# proto3.net
KiCad netlist of a schematic drawn in EAGLE
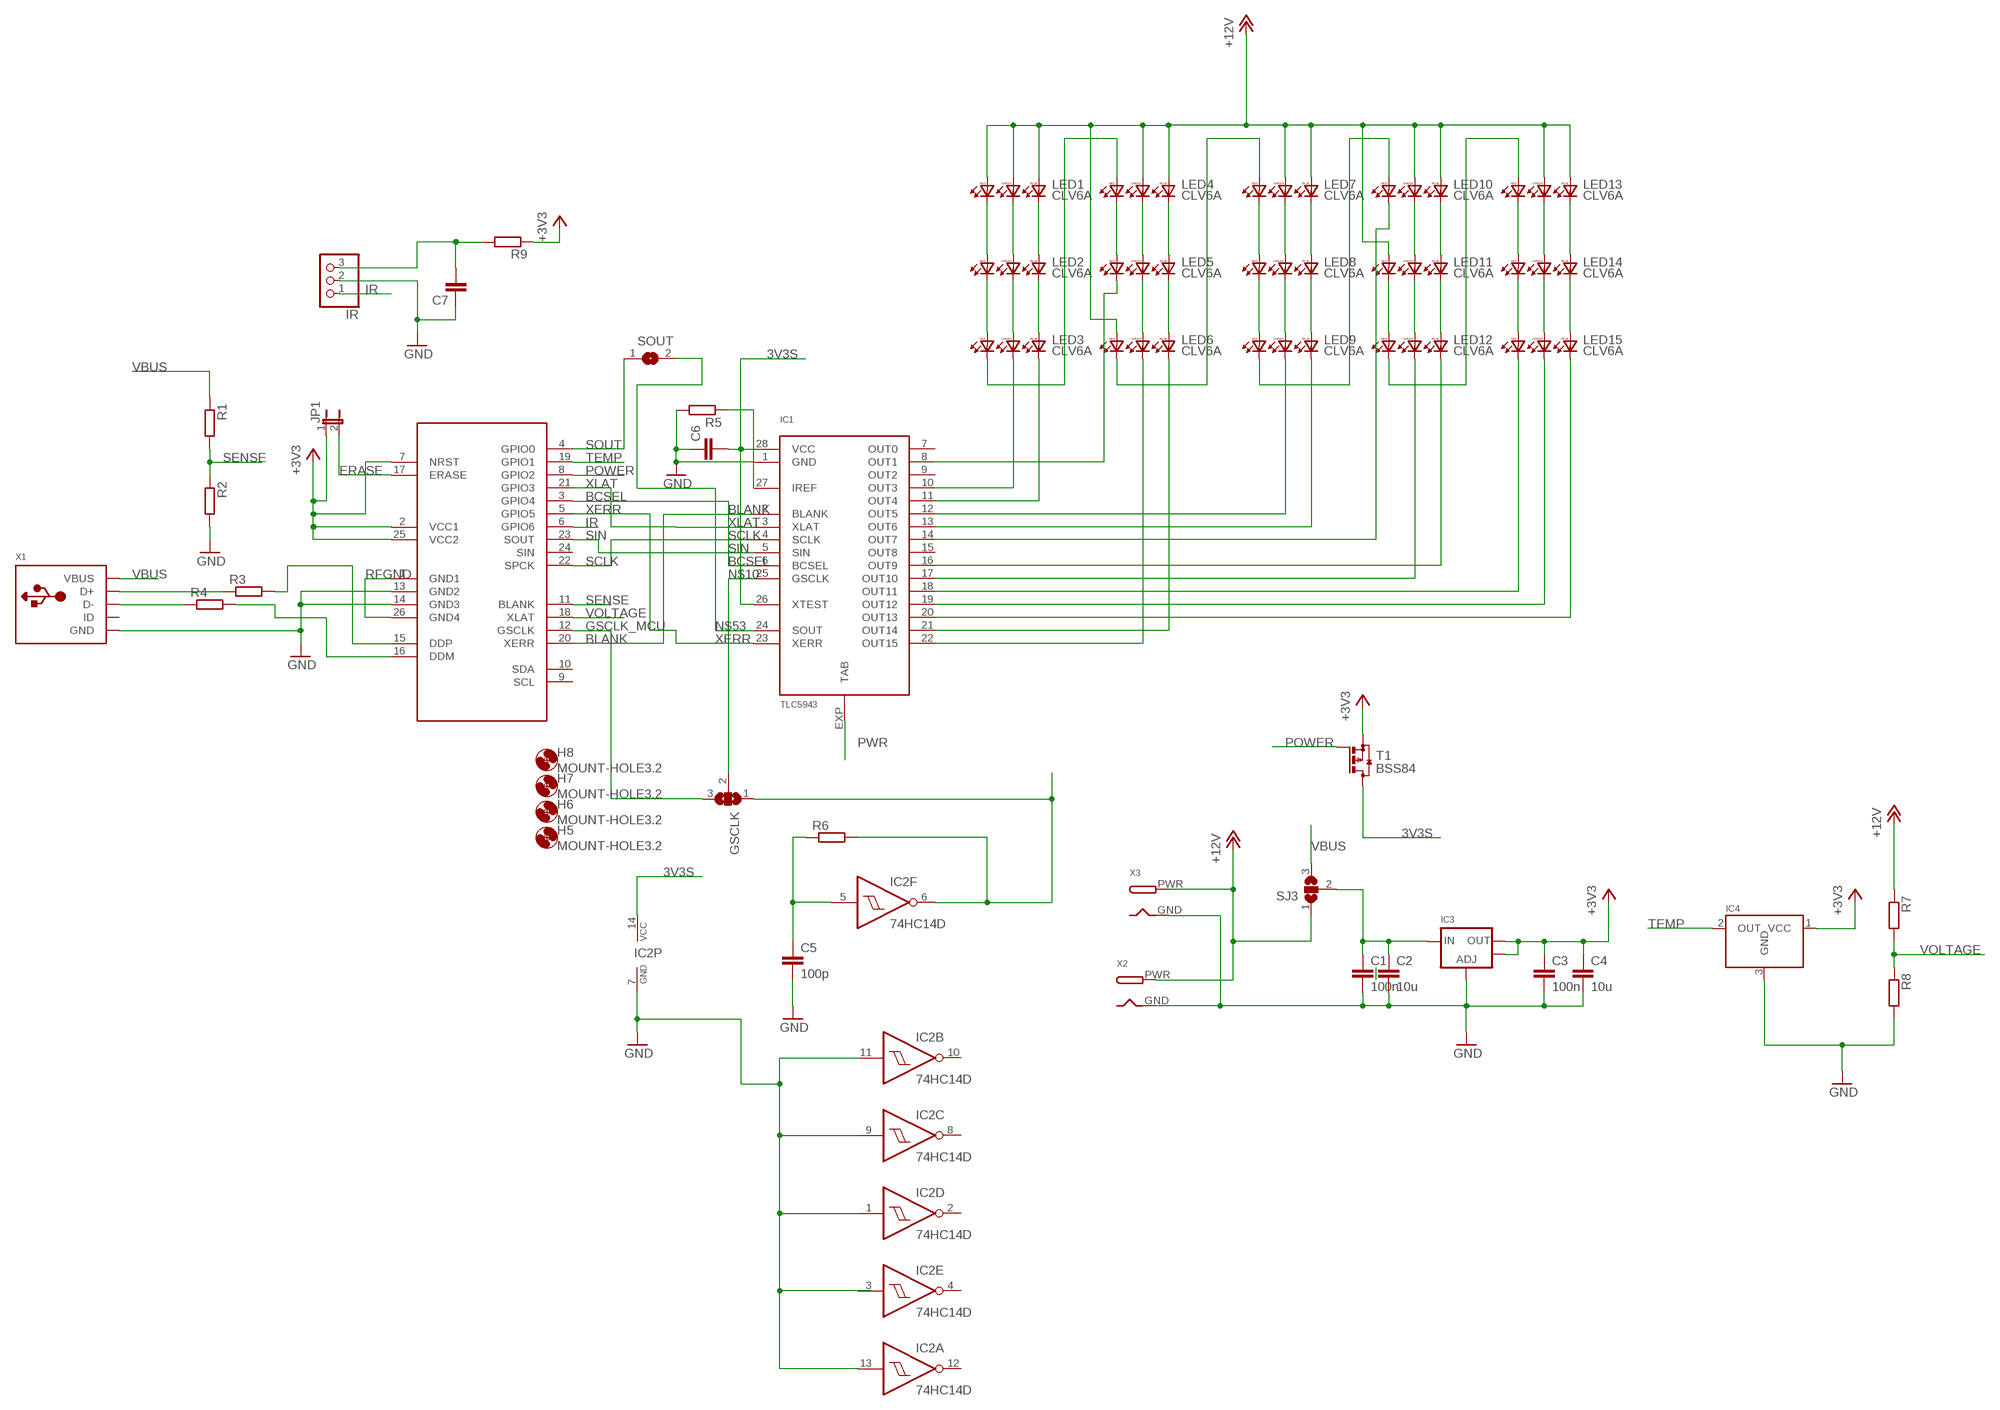
[diagram p0: schematic, sheet 1]

(export (version "E")
  (design (tool "Eeschema 10.0.6"))
  (components
    (comp (ref "C1")
      (value "100n")
      (footprint "eagle-import:C0805")
      (libsource (lib "eagle-import") (part "C-EUC0805"))
    )
    (comp (ref "C2")
      (value "10u")
      (footprint "eagle-import:C0805")
      (libsource (lib "eagle-import") (part "C-EUC0805"))
    )
    (comp (ref "C3")
      (value "100n")
      (footprint "eagle-import:C0805")
      (libsource (lib "eagle-import") (part "C-EUC0805"))
    )
    (comp (ref "C4")
      (value "10u")
      (footprint "eagle-import:C0805")
      (libsource (lib "eagle-import") (part "C-EUC0805"))
    )
    (comp (ref "C5")
      (value "100p")
      (footprint "eagle-import:C0805")
      (libsource (lib "eagle-import") (part "C-EUC0805"))
    )
    (comp (ref "C6")
      (value "C-EUC0805")
      (footprint "eagle-import:C0805")
      (libsource (lib "eagle-import") (part "C-EUC0805"))
    )
    (comp (ref "C7")
      (value "C-EUC0805")
      (footprint "eagle-import:C0805")
      (libsource (lib "eagle-import") (part "C-EUC0805"))
    )
    (comp (ref "GSCLK")
      (value "SJ2W")
      (footprint "eagle-import:SJ_2")
      (libsource (lib "eagle-import") (part "SJ2W"))
    )
    (comp (ref "H5")
      (value "MOUNT-HOLE3.2")
      (footprint "eagle-import:3,2")
      (libsource (lib "eagle-import") (part "MOUNT-HOLE3.2"))
    )
    (comp (ref "H6")
      (value "MOUNT-HOLE3.2")
      (footprint "eagle-import:3,2")
      (libsource (lib "eagle-import") (part "MOUNT-HOLE3.2"))
    )
    (comp (ref "H7")
      (value "MOUNT-HOLE3.2")
      (footprint "eagle-import:3,2")
      (libsource (lib "eagle-import") (part "MOUNT-HOLE3.2"))
    )
    (comp (ref "H8")
      (value "MOUNT-HOLE3.2")
      (footprint "eagle-import:3,2")
      (libsource (lib "eagle-import") (part "MOUNT-HOLE3.2"))
    )
    (comp (ref "IC1")
      (value "TLC5943")
      (footprint "eagle-import:HTSSOP28PWP")
      (libsource (lib "eagle-import") (part "TLC5943"))
    )
    (comp (ref "IC2")
      (value "74HC14D")
      (footprint "eagle-import:SO14")
      (libsource (lib "eagle-import") (part "7414DHC"))
    )
    (comp (ref "IC3")
      (value "LM1117SOT223-REFLOW")
      (footprint "eagle-import:SOT223-R")
      (libsource (lib "eagle-import") (part "LM1117SOT223-REFLOW"))
    )
    (comp (ref "IC4")
      (value "MCP9701T-E/TTCTREFLOW")
      (footprint "eagle-import:SOT23-R")
      (libsource (lib "eagle-import") (part "MCP9701T-E/TTCTREFLOW"))
    )
    (comp (ref "IR")
      (value "PINHD-1X3")
      (footprint "eagle-import:1X03")
      (libsource (lib "eagle-import") (part "PINHD-1X3"))
    )
    (comp (ref "JP1")
      (value "JP1E")
      (footprint "eagle-import:JP1")
      (libsource (lib "eagle-import") (part "JP1E"))
    )
    (comp (ref "LED1")
      (value "CLV6A")
      (footprint "eagle-import:PLCC6")
      (libsource (lib "eagle-import") (part "CLV6A"))
    )
    (comp (ref "LED2")
      (value "CLV6A")
      (footprint "eagle-import:PLCC6")
      (libsource (lib "eagle-import") (part "CLV6A"))
    )
    (comp (ref "LED3")
      (value "CLV6A")
      (footprint "eagle-import:PLCC6")
      (libsource (lib "eagle-import") (part "CLV6A"))
    )
    (comp (ref "LED4")
      (value "CLV6A")
      (footprint "eagle-import:PLCC6")
      (libsource (lib "eagle-import") (part "CLV6A"))
    )
    (comp (ref "LED5")
      (value "CLV6A")
      (footprint "eagle-import:PLCC6")
      (libsource (lib "eagle-import") (part "CLV6A"))
    )
    (comp (ref "LED6")
      (value "CLV6A")
      (footprint "eagle-import:PLCC6")
      (libsource (lib "eagle-import") (part "CLV6A"))
    )
    (comp (ref "LED7")
      (value "CLV6A")
      (footprint "eagle-import:PLCC6")
      (libsource (lib "eagle-import") (part "CLV6A"))
    )
    (comp (ref "LED8")
      (value "CLV6A")
      (footprint "eagle-import:PLCC6")
      (libsource (lib "eagle-import") (part "CLV6A"))
    )
    (comp (ref "LED9")
      (value "CLV6A")
      (footprint "eagle-import:PLCC6")
      (libsource (lib "eagle-import") (part "CLV6A"))
    )
    (comp (ref "LED10")
      (value "CLV6A")
      (footprint "eagle-import:PLCC6")
      (libsource (lib "eagle-import") (part "CLV6A"))
    )
    (comp (ref "LED11")
      (value "CLV6A")
      (footprint "eagle-import:PLCC6")
      (libsource (lib "eagle-import") (part "CLV6A"))
    )
    (comp (ref "LED12")
      (value "CLV6A")
      (footprint "eagle-import:PLCC6")
      (libsource (lib "eagle-import") (part "CLV6A"))
    )
    (comp (ref "LED13")
      (value "CLV6A")
      (footprint "eagle-import:PLCC6")
      (libsource (lib "eagle-import") (part "CLV6A"))
    )
    (comp (ref "LED14")
      (value "CLV6A")
      (footprint "eagle-import:PLCC6")
      (libsource (lib "eagle-import") (part "CLV6A"))
    )
    (comp (ref "LED15")
      (value "CLV6A")
      (footprint "eagle-import:PLCC6")
      (libsource (lib "eagle-import") (part "CLV6A"))
    )
    (comp (ref "R1")
      (value "R-EU_R0805")
      (footprint "eagle-import:R0805")
      (libsource (lib "eagle-import") (part "R-EU_R0805"))
    )
    (comp (ref "R2")
      (value "R-EU_R0805")
      (footprint "eagle-import:R0805")
      (libsource (lib "eagle-import") (part "R-EU_R0805"))
    )
    (comp (ref "R3")
      (value "R-EU_R0805")
      (footprint "eagle-import:R0805")
      (libsource (lib "eagle-import") (part "R-EU_R0805"))
    )
    (comp (ref "R4")
      (value "R-EU_R0805")
      (footprint "eagle-import:R0805")
      (libsource (lib "eagle-import") (part "R-EU_R0805"))
    )
    (comp (ref "R5")
      (value "R-EU_R0805")
      (footprint "eagle-import:R0805")
      (libsource (lib "eagle-import") (part "R-EU_R0805"))
    )
    (comp (ref "R6")
      (value "R-EU_R0805")
      (footprint "eagle-import:R0805")
      (libsource (lib "eagle-import") (part "R-EU_R0805"))
    )
    (comp (ref "R7")
      (value "R-EU_R0805")
      (footprint "eagle-import:R0805")
      (libsource (lib "eagle-import") (part "R-EU_R0805"))
    )
    (comp (ref "R8")
      (value "R-EU_R0805")
      (footprint "eagle-import:R0805")
      (libsource (lib "eagle-import") (part "R-EU_R0805"))
    )
    (comp (ref "R9")
      (value "R-EU_R0805")
      (footprint "eagle-import:R0805")
      (libsource (lib "eagle-import") (part "R-EU_R0805"))
    )
    (comp (ref "SJ3")
      (value "SJ2W")
      (footprint "eagle-import:SJ_2")
      (libsource (lib "eagle-import") (part "SJ2W"))
    )
    (comp (ref "SOUT")
      (value "SJ")
      (footprint "eagle-import:SJ")
      (libsource (lib "eagle-import") (part "SJ"))
    )
    (comp (ref "T1")
      (value "BSS84")
      (footprint "eagle-import:SOT23")
      (libsource (lib "eagle-import") (part "BSS84"))
    )
    (comp (ref "U$1")
      (value "RFBOARD")
      (footprint "eagle-import:RFBOARD")
      (libsource (lib "eagle-import") (part "RFBOARD"))
    )
    (comp (ref "X1")
      (value "USBMINIB")
      (footprint "eagle-import:USB-MINIB")
      (libsource (lib "eagle-import") (part "USBMINIB"))
    )
    (comp (ref "X2")
      (value "DCBARRELPTH")
      (footprint "eagle-import:DCJACK_2MM_PTH")
      (libsource (lib "eagle-import") (part "DCBARRELPTH"))
    )
    (comp (ref "X3")
      (value "DCBARRELPTH")
      (footprint "eagle-import:DCJACK_2MM_PTH")
      (libsource (lib "eagle-import") (part "DCBARRELPTH"))
    )
  )
  (nets
    (net (code "1") (name "+3V3") (class "Default")
      (node (ref "C3") (pin "1") (pinfunction "1_1") (pintype "passive"))
      (node (ref "C4") (pin "1") (pinfunction "1_1") (pintype "passive"))
      (node (ref "IC3") (pin "2") (pinfunction "OUT_2") (pintype "passive"))
      (node (ref "IC3") (pin "4") (pinfunction "OUT1_4") (pintype "passive"))
      (node (ref "IC4") (pin "1") (pinfunction "VCC_1") (pintype "power_in"))
      (node (ref "JP1") (pin "1") (pinfunction "1_1") (pintype "passive"))
      (node (ref "R9") (pin "1") (pinfunction "1_1") (pintype "passive"))
      (node (ref "T1") (pin "2") (pinfunction "S_2") (pintype "passive"))
      (node (ref "U$1") (pin "2") (pinfunction "VCC1_2") (pintype "bidirectional"))
      (node (ref "U$1") (pin "25") (pinfunction "VCC2_25") (pintype "bidirectional"))
      (node (ref "U$1") (pin "7") (pinfunction "NRST_7") (pintype "bidirectional"))
    )
    (net (code "2") (name "+12V") (class "Default")
      (node (ref "LED1") (pin "4") (pinfunction "RA_4") (pintype "passive"))
      (node (ref "LED1") (pin "5") (pinfunction "GA_5") (pintype "passive"))
      (node (ref "LED1") (pin "6") (pinfunction "BA_6") (pintype "passive"))
      (node (ref "LED10") (pin "5") (pinfunction "GA_5") (pintype "passive"))
      (node (ref "LED10") (pin "6") (pinfunction "BA_6") (pintype "passive"))
      (node (ref "LED11") (pin "4") (pinfunction "RA_4") (pintype "passive"))
      (node (ref "LED13") (pin "5") (pinfunction "GA_5") (pintype "passive"))
      (node (ref "LED13") (pin "6") (pinfunction "BA_6") (pintype "passive"))
      (node (ref "LED4") (pin "5") (pinfunction "GA_5") (pintype "passive"))
      (node (ref "LED4") (pin "6") (pinfunction "BA_6") (pintype "passive"))
      (node (ref "LED6") (pin "4") (pinfunction "RA_4") (pintype "passive"))
      (node (ref "LED7") (pin "5") (pinfunction "GA_5") (pintype "passive"))
      (node (ref "LED7") (pin "6") (pinfunction "BA_6") (pintype "passive"))
      (node (ref "R7") (pin "1") (pinfunction "1_1") (pintype "passive"))
      (node (ref "SJ3") (pin "1") (pinfunction "1_1") (pintype "passive"))
      (node (ref "X2") (pin "PWR") (pinfunction "PWR_PWR") (pintype "power_in"))
      (node (ref "X3") (pin "PWR") (pinfunction "PWR_PWR") (pintype "power_in"))
    )
    (net (code "3") (name "/3V3S") (class "Default")
      (node (ref "C6") (pin "2") (pinfunction "2_2") (pintype "passive"))
      (node (ref "IC1") (pin "26") (pinfunction "XTEST_26") (pintype "bidirectional"))
      (node (ref "IC1") (pin "28") (pinfunction "VCC_28") (pintype "bidirectional"))
      (node (ref "IC2") (pin "14") (pinfunction "VCC_14") (pintype "power_in"))
      (node (ref "T1") (pin "3") (pinfunction "D_3") (pintype "passive"))
    )
    (net (code "4") (name "/BCSEL") (class "Default")
      (node (ref "IC1") (pin "6") (pinfunction "BCSEL_6") (pintype "bidirectional"))
      (node (ref "U$1") (pin "3") (pinfunction "GPIO4_3") (pintype "bidirectional"))
    )
    (net (code "5") (name "/BLANK") (class "Default")
      (node (ref "IC1") (pin "2") (pinfunction "BLANK_2") (pintype "bidirectional"))
      (node (ref "U$1") (pin "20") (pinfunction "XERR_20") (pintype "bidirectional"))
    )
    (net (code "6") (name "/ERASE") (class "Default")
      (node (ref "JP1") (pin "2") (pinfunction "2_2") (pintype "passive"))
      (node (ref "U$1") (pin "17") (pinfunction "ERASE_17") (pintype "bidirectional"))
    )
    (net (code "7") (name "/GSCLK_MCU") (class "Default")
      (node (ref "GSCLK") (pin "3") (pinfunction "3_3") (pintype "passive"))
      (node (ref "U$1") (pin "12") (pinfunction "GSCLK_12") (pintype "bidirectional"))
    )
    (net (code "8") (name "/IR") (class "Default")
      (node (ref "IR") (pin "1") (pinfunction "1_1") (pintype "passive"))
      (node (ref "U$1") (pin "6") (pinfunction "GPIO6_6") (pintype "bidirectional"))
    )
    (net (code "9") (name "/N$10") (class "Default")
      (node (ref "GSCLK") (pin "2") (pinfunction "2_2") (pintype "passive"))
      (node (ref "IC1") (pin "25") (pinfunction "GSCLK_25") (pintype "bidirectional"))
    )
    (net (code "10") (name "/N$53") (class "Default")
      (node (ref "IC1") (pin "24") (pinfunction "SOUT_24") (pintype "bidirectional"))
      (node (ref "SOUT") (pin "2") (pinfunction "2_2") (pintype "passive"))
    )
    (net (code "11") (name "/POWER") (class "Default")
      (node (ref "T1") (pin "1") (pinfunction "G_1") (pintype "passive"))
      (node (ref "U$1") (pin "8") (pinfunction "GPIO2_8") (pintype "bidirectional"))
    )
    (net (code "12") (name "/PWR") (class "Default")
      (node (ref "IC1") (pin "EXP") (pinfunction "TAB_EXP") (pintype "bidirectional"))
    )
    (net (code "13") (name "/RFGND") (class "Default")
      (node (ref "U$1") (pin "1") (pinfunction "GND1_1") (pintype "bidirectional"))
      (node (ref "U$1") (pin "26") (pinfunction "GND4_26") (pintype "bidirectional"))
    )
    (net (code "14") (name "/SCLK") (class "Default")
      (node (ref "IC1") (pin "4") (pinfunction "SCLK_4") (pintype "bidirectional"))
      (node (ref "U$1") (pin "22") (pinfunction "SPCK_22") (pintype "bidirectional"))
    )
    (net (code "15") (name "/SENSE") (class "Default")
      (node (ref "R1") (pin "2") (pinfunction "2_2") (pintype "passive"))
      (node (ref "R2") (pin "1") (pinfunction "1_1") (pintype "passive"))
      (node (ref "U$1") (pin "11") (pinfunction "BLANK_11") (pintype "bidirectional"))
    )
    (net (code "16") (name "/SIN") (class "Default")
      (node (ref "IC1") (pin "5") (pinfunction "SIN_5") (pintype "bidirectional"))
      (node (ref "U$1") (pin "23") (pinfunction "SOUT_23") (pintype "bidirectional"))
    )
    (net (code "17") (name "/SOUT") (class "Default")
      (node (ref "SOUT") (pin "1") (pinfunction "1_1") (pintype "passive"))
      (node (ref "U$1") (pin "4") (pinfunction "GPIO0_4") (pintype "bidirectional"))
    )
    (net (code "18") (name "/TEMP") (class "Default")
      (node (ref "IC4") (pin "2") (pinfunction "OUT_2") (pintype "bidirectional"))
      (node (ref "U$1") (pin "19") (pinfunction "GPIO1_19") (pintype "bidirectional"))
    )
    (net (code "19") (name "/VBUS") (class "Default")
      (node (ref "R1") (pin "1") (pinfunction "1_1") (pintype "passive"))
      (node (ref "SJ3") (pin "3") (pinfunction "3_3") (pintype "passive"))
      (node (ref "X1") (pin "VBUS") (pinfunction "VBUS_VBUS") (pintype "power_in"))
    )
    (net (code "20") (name "/VOLTAGE") (class "Default")
      (node (ref "R7") (pin "2") (pinfunction "2_2") (pintype "passive"))
      (node (ref "R8") (pin "1") (pinfunction "1_1") (pintype "passive"))
      (node (ref "U$1") (pin "18") (pinfunction "XLAT_18") (pintype "bidirectional"))
    )
    (net (code "21") (name "/XERR") (class "Default")
      (node (ref "IC1") (pin "23") (pinfunction "XERR_23") (pintype "bidirectional"))
      (node (ref "U$1") (pin "5") (pinfunction "GPIO5_5") (pintype "bidirectional"))
    )
    (net (code "22") (name "/XLAT") (class "Default")
      (node (ref "IC1") (pin "3") (pinfunction "XLAT_3") (pintype "bidirectional"))
      (node (ref "U$1") (pin "21") (pinfunction "GPIO3_21") (pintype "bidirectional"))
    )
    (net (code "23") (name "GND") (class "Default")
      (node (ref "C1") (pin "2") (pinfunction "2_2") (pintype "passive"))
      (node (ref "C2") (pin "2") (pinfunction "2_2") (pintype "passive"))
      (node (ref "C3") (pin "2") (pinfunction "2_2") (pintype "passive"))
      (node (ref "C4") (pin "2") (pinfunction "2_2") (pintype "passive"))
      (node (ref "C5") (pin "2") (pinfunction "2_2") (pintype "passive"))
      (node (ref "C6") (pin "1") (pinfunction "1_1") (pintype "passive"))
      (node (ref "C7") (pin "1") (pinfunction "1_1") (pintype "passive"))
      (node (ref "IC1") (pin "1") (pinfunction "GND_1") (pintype "bidirectional"))
      (node (ref "IC2") (pin "1") (pinfunction "I_1") (pintype "input"))
      (node (ref "IC2") (pin "11") (pinfunction "I_11") (pintype "input"))
      (node (ref "IC2") (pin "13") (pinfunction "I_13") (pintype "input"))
      (node (ref "IC2") (pin "7") (pinfunction "GND_7") (pintype "power_in"))
      (node (ref "IC2") (pin "9") (pinfunction "I_9") (pintype "input"))
      (node (ref "IC3") (pin "1") (pinfunction "ADJ_1") (pintype "input"))
      (node (ref "IC4") (pin "3") (pinfunction "GND_3") (pintype "power_in"))
      (node (ref "IR") (pin "2") (pinfunction "2_2") (pintype "passive"))
      (node (ref "R2") (pin "2") (pinfunction "2_2") (pintype "passive"))
      (node (ref "R5") (pin "2") (pinfunction "2_2") (pintype "passive"))
      (node (ref "R8") (pin "2") (pinfunction "2_2") (pintype "passive"))
      (node (ref "U$1") (pin "13") (pinfunction "GND2_13") (pintype "bidirectional"))
      (node (ref "U$1") (pin "14") (pinfunction "GND3_14") (pintype "bidirectional"))
      (node (ref "X1") (pin "GND") (pinfunction "GND_GND") (pintype "power_in"))
      (node (ref "X2") (pin "GND") (pinfunction "GND_GND") (pintype "power_in"))
      (node (ref "X3") (pin "GND") (pinfunction "GND_GND") (pintype "power_in"))
    )
    (net (code "24") (name "Net-(C7-Pad2)") (class "Default")
      (node (ref "C7") (pin "2") (pinfunction "2_2") (pintype "passive"))
      (node (ref "IR") (pin "3") (pinfunction "3_3") (pintype "passive"))
      (node (ref "R9") (pin "2") (pinfunction "2_2") (pintype "passive"))
    )
    (net (code "25") (name "Net-(IC1-IREF)") (class "Default")
      (node (ref "IC1") (pin "27") (pinfunction "IREF_27") (pintype "bidirectional"))
      (node (ref "R5") (pin "1") (pinfunction "1_1") (pintype "passive"))
    )
    (net (code "26") (name "Net-(IC1-OUT1)") (class "Default")
      (node (ref "IC1") (pin "8") (pinfunction "OUT1_8") (pintype "bidirectional"))
      (node (ref "LED5") (pin "3") (pinfunction "RC_3") (pintype "passive"))
    )
    (net (code "27") (name "Net-(IC1-OUT3)") (class "Default")
      (node (ref "IC1") (pin "10") (pinfunction "OUT3_10") (pintype "bidirectional"))
      (node (ref "LED3") (pin "2") (pinfunction "GC_2") (pintype "passive"))
    )
    (net (code "28") (name "Net-(IC1-OUT4)") (class "Default")
      (node (ref "IC1") (pin "11") (pinfunction "OUT4_11") (pintype "bidirectional"))
      (node (ref "LED3") (pin "1") (pinfunction "BC_1") (pintype "passive"))
    )
    (net (code "29") (name "Net-(IC1-OUT5)") (class "Default")
      (node (ref "IC1") (pin "12") (pinfunction "OUT5_12") (pintype "bidirectional"))
      (node (ref "LED9") (pin "2") (pinfunction "GC_2") (pintype "passive"))
    )
    (net (code "30") (name "Net-(IC1-OUT6)") (class "Default")
      (node (ref "IC1") (pin "13") (pinfunction "OUT6_13") (pintype "bidirectional"))
      (node (ref "LED9") (pin "1") (pinfunction "BC_1") (pintype "passive"))
    )
    (net (code "31") (name "Net-(IC1-OUT7)") (class "Default")
      (node (ref "IC1") (pin "14") (pinfunction "OUT7_14") (pintype "bidirectional"))
      (node (ref "LED10") (pin "3") (pinfunction "RC_3") (pintype "passive"))
    )
    (net (code "32") (name "Net-(IC1-OUT9)") (class "Default")
      (node (ref "IC1") (pin "16") (pinfunction "OUT9_16") (pintype "bidirectional"))
      (node (ref "LED12") (pin "1") (pinfunction "BC_1") (pintype "passive"))
    )
    (net (code "33") (name "Net-(IC1-OUT10)") (class "Default")
      (node (ref "IC1") (pin "17") (pinfunction "OUT10_17") (pintype "bidirectional"))
      (node (ref "LED12") (pin "2") (pinfunction "GC_2") (pintype "passive"))
    )
    (net (code "34") (name "Net-(IC1-OUT11)") (class "Default")
      (node (ref "IC1") (pin "18") (pinfunction "OUT11_18") (pintype "bidirectional"))
      (node (ref "LED15") (pin "3") (pinfunction "RC_3") (pintype "passive"))
    )
    (net (code "35") (name "Net-(IC1-OUT12)") (class "Default")
      (node (ref "IC1") (pin "19") (pinfunction "OUT12_19") (pintype "bidirectional"))
      (node (ref "LED15") (pin "2") (pinfunction "GC_2") (pintype "passive"))
    )
    (net (code "36") (name "Net-(IC1-OUT13)") (class "Default")
      (node (ref "IC1") (pin "20") (pinfunction "OUT13_20") (pintype "bidirectional"))
      (node (ref "LED15") (pin "1") (pinfunction "BC_1") (pintype "passive"))
    )
    (net (code "37") (name "Net-(IC1-OUT14)") (class "Default")
      (node (ref "IC1") (pin "21") (pinfunction "OUT14_21") (pintype "bidirectional"))
      (node (ref "LED6") (pin "1") (pinfunction "BC_1") (pintype "passive"))
    )
    (net (code "38") (name "Net-(IC1-OUT15)") (class "Default")
      (node (ref "IC1") (pin "22") (pinfunction "OUT15_22") (pintype "bidirectional"))
      (node (ref "LED6") (pin "2") (pinfunction "GC_2") (pintype "passive"))
    )
    (net (code "39") (name "Net-(IC2F-I)") (class "Default")
      (node (ref "C5") (pin "1") (pinfunction "1_1") (pintype "passive"))
      (node (ref "IC2") (pin "5") (pinfunction "I_5") (pintype "input"))
      (node (ref "R6") (pin "1") (pinfunction "1_1") (pintype "passive"))
    )
    (net (code "40") (name "Net-(IC2F-O)") (class "Default")
      (node (ref "GSCLK") (pin "1") (pinfunction "1_1") (pintype "passive"))
      (node (ref "IC2") (pin "6") (pinfunction "O_6") (pintype "output"))
      (node (ref "R6") (pin "2") (pinfunction "2_2") (pintype "passive"))
    )
    (net (code "41") (name "Net-(IC3-IN)") (class "Default")
      (node (ref "C1") (pin "1") (pinfunction "1_1") (pintype "passive"))
      (node (ref "C2") (pin "1") (pinfunction "1_1") (pintype "passive"))
      (node (ref "IC3") (pin "3") (pinfunction "IN_3") (pintype "input"))
      (node (ref "SJ3") (pin "2") (pinfunction "2_2") (pintype "passive"))
    )
    (net (code "42") (name "Net-(LED1-BC)") (class "Default")
      (node (ref "LED1") (pin "1") (pinfunction "BC_1") (pintype "passive"))
      (node (ref "LED2") (pin "6") (pinfunction "BA_6") (pintype "passive"))
    )
    (net (code "43") (name "Net-(LED1-GC)") (class "Default")
      (node (ref "LED1") (pin "2") (pinfunction "GC_2") (pintype "passive"))
      (node (ref "LED2") (pin "5") (pinfunction "GA_5") (pintype "passive"))
    )
    (net (code "44") (name "Net-(LED1-RC)") (class "Default")
      (node (ref "LED1") (pin "3") (pinfunction "RC_3") (pintype "passive"))
      (node (ref "LED2") (pin "4") (pinfunction "RA_4") (pintype "passive"))
    )
    (net (code "45") (name "Net-(LED2-BC)") (class "Default")
      (node (ref "LED2") (pin "1") (pinfunction "BC_1") (pintype "passive"))
      (node (ref "LED3") (pin "6") (pinfunction "BA_6") (pintype "passive"))
    )
    (net (code "46") (name "Net-(LED2-GC)") (class "Default")
      (node (ref "LED2") (pin "2") (pinfunction "GC_2") (pintype "passive"))
      (node (ref "LED3") (pin "5") (pinfunction "GA_5") (pintype "passive"))
    )
    (net (code "47") (name "Net-(LED2-RC)") (class "Default")
      (node (ref "LED2") (pin "3") (pinfunction "RC_3") (pintype "passive"))
      (node (ref "LED3") (pin "4") (pinfunction "RA_4") (pintype "passive"))
    )
    (net (code "48") (name "Net-(LED3-RC)") (class "Default")
      (node (ref "LED3") (pin "3") (pinfunction "RC_3") (pintype "passive"))
      (node (ref "LED4") (pin "4") (pinfunction "RA_4") (pintype "passive"))
    )
    (net (code "49") (name "Net-(LED4-BC)") (class "Default")
      (node (ref "LED4") (pin "1") (pinfunction "BC_1") (pintype "passive"))
      (node (ref "LED5") (pin "6") (pinfunction "BA_6") (pintype "passive"))
    )
    (net (code "50") (name "Net-(LED4-GC)") (class "Default")
      (node (ref "LED4") (pin "2") (pinfunction "GC_2") (pintype "passive"))
      (node (ref "LED5") (pin "5") (pinfunction "GA_5") (pintype "passive"))
    )
    (net (code "51") (name "Net-(LED4-RC)") (class "Default")
      (node (ref "LED4") (pin "3") (pinfunction "RC_3") (pintype "passive"))
      (node (ref "LED5") (pin "4") (pinfunction "RA_4") (pintype "passive"))
    )
    (net (code "52") (name "Net-(LED5-BC)") (class "Default")
      (node (ref "LED5") (pin "1") (pinfunction "BC_1") (pintype "passive"))
      (node (ref "LED6") (pin "6") (pinfunction "BA_6") (pintype "passive"))
    )
    (net (code "53") (name "Net-(LED5-GC)") (class "Default")
      (node (ref "LED5") (pin "2") (pinfunction "GC_2") (pintype "passive"))
      (node (ref "LED6") (pin "5") (pinfunction "GA_5") (pintype "passive"))
    )
    (net (code "54") (name "Net-(LED6-RC)") (class "Default")
      (node (ref "LED6") (pin "3") (pinfunction "RC_3") (pintype "passive"))
      (node (ref "LED7") (pin "4") (pinfunction "RA_4") (pintype "passive"))
    )
    (net (code "55") (name "Net-(LED7-BC)") (class "Default")
      (node (ref "LED7") (pin "1") (pinfunction "BC_1") (pintype "passive"))
      (node (ref "LED8") (pin "6") (pinfunction "BA_6") (pintype "passive"))
    )
    (net (code "56") (name "Net-(LED7-GC)") (class "Default")
      (node (ref "LED7") (pin "2") (pinfunction "GC_2") (pintype "passive"))
      (node (ref "LED8") (pin "5") (pinfunction "GA_5") (pintype "passive"))
    )
    (net (code "57") (name "Net-(LED7-RC)") (class "Default")
      (node (ref "LED7") (pin "3") (pinfunction "RC_3") (pintype "passive"))
      (node (ref "LED8") (pin "4") (pinfunction "RA_4") (pintype "passive"))
    )
    (net (code "58") (name "Net-(LED8-BC)") (class "Default")
      (node (ref "LED8") (pin "1") (pinfunction "BC_1") (pintype "passive"))
      (node (ref "LED9") (pin "6") (pinfunction "BA_6") (pintype "passive"))
    )
    (net (code "59") (name "Net-(LED8-GC)") (class "Default")
      (node (ref "LED8") (pin "2") (pinfunction "GC_2") (pintype "passive"))
      (node (ref "LED9") (pin "5") (pinfunction "GA_5") (pintype "passive"))
    )
    (net (code "60") (name "Net-(LED8-RC)") (class "Default")
      (node (ref "LED8") (pin "3") (pinfunction "RC_3") (pintype "passive"))
      (node (ref "LED9") (pin "4") (pinfunction "RA_4") (pintype "passive"))
    )
    (net (code "61") (name "Net-(LED10-BC)") (class "Default")
      (node (ref "LED10") (pin "1") (pinfunction "BC_1") (pintype "passive"))
      (node (ref "LED11") (pin "6") (pinfunction "BA_6") (pintype "passive"))
    )
    (net (code "62") (name "Net-(LED10-GC)") (class "Default")
      (node (ref "LED10") (pin "2") (pinfunction "GC_2") (pintype "passive"))
      (node (ref "LED11") (pin "5") (pinfunction "GA_5") (pintype "passive"))
    )
    (net (code "63") (name "Net-(LED10-RA)") (class "Default")
      (node (ref "LED10") (pin "4") (pinfunction "RA_4") (pintype "passive"))
      (node (ref "LED9") (pin "3") (pinfunction "RC_3") (pintype "passive"))
    )
    (net (code "64") (name "Net-(LED11-BC)") (class "Default")
      (node (ref "LED11") (pin "1") (pinfunction "BC_1") (pintype "passive"))
      (node (ref "LED12") (pin "6") (pinfunction "BA_6") (pintype "passive"))
    )
    (net (code "65") (name "Net-(LED11-GC)") (class "Default")
      (node (ref "LED11") (pin "2") (pinfunction "GC_2") (pintype "passive"))
      (node (ref "LED12") (pin "5") (pinfunction "GA_5") (pintype "passive"))
    )
    (net (code "66") (name "Net-(LED11-RC)") (class "Default")
      (node (ref "LED11") (pin "3") (pinfunction "RC_3") (pintype "passive"))
      (node (ref "LED12") (pin "4") (pinfunction "RA_4") (pintype "passive"))
    )
    (net (code "67") (name "Net-(LED12-RC)") (class "Default")
      (node (ref "LED12") (pin "3") (pinfunction "RC_3") (pintype "passive"))
      (node (ref "LED13") (pin "4") (pinfunction "RA_4") (pintype "passive"))
    )
    (net (code "68") (name "Net-(LED13-BC)") (class "Default")
      (node (ref "LED13") (pin "1") (pinfunction "BC_1") (pintype "passive"))
      (node (ref "LED14") (pin "6") (pinfunction "BA_6") (pintype "passive"))
    )
    (net (code "69") (name "Net-(LED13-GC)") (class "Default")
      (node (ref "LED13") (pin "2") (pinfunction "GC_2") (pintype "passive"))
      (node (ref "LED14") (pin "5") (pinfunction "GA_5") (pintype "passive"))
    )
    (net (code "70") (name "Net-(LED13-RC)") (class "Default")
      (node (ref "LED13") (pin "3") (pinfunction "RC_3") (pintype "passive"))
      (node (ref "LED14") (pin "4") (pinfunction "RA_4") (pintype "passive"))
    )
    (net (code "71") (name "Net-(LED14-BC)") (class "Default")
      (node (ref "LED14") (pin "1") (pinfunction "BC_1") (pintype "passive"))
      (node (ref "LED15") (pin "6") (pinfunction "BA_6") (pintype "passive"))
    )
    (net (code "72") (name "Net-(LED14-GC)") (class "Default")
      (node (ref "LED14") (pin "2") (pinfunction "GC_2") (pintype "passive"))
      (node (ref "LED15") (pin "5") (pinfunction "GA_5") (pintype "passive"))
    )
    (net (code "73") (name "Net-(LED14-RC)") (class "Default")
      (node (ref "LED14") (pin "3") (pinfunction "RC_3") (pintype "passive"))
      (node (ref "LED15") (pin "4") (pinfunction "RA_4") (pintype "passive"))
    )
    (net (code "74") (name "Net-(R3-Pad1)") (class "Default")
      (node (ref "R3") (pin "1") (pinfunction "1_1") (pintype "passive"))
      (node (ref "X1") (pin "D+") (pinfunction "D+_D+") (pintype "bidirectional"))
    )
    (net (code "75") (name "Net-(R4-Pad1)") (class "Default")
      (node (ref "R4") (pin "1") (pinfunction "1_1") (pintype "passive"))
      (node (ref "X1") (pin "D-") (pinfunction "D-_D-") (pintype "bidirectional"))
    )
    (net (code "76") (name "Net-(U$1-DDM)") (class "Default")
      (node (ref "R4") (pin "2") (pinfunction "2_2") (pintype "passive"))
      (node (ref "U$1") (pin "16") (pinfunction "DDM_16") (pintype "bidirectional"))
    )
    (net (code "77") (name "Net-(U$1-DDP)") (class "Default")
      (node (ref "R3") (pin "2") (pinfunction "2_2") (pintype "passive"))
      (node (ref "U$1") (pin "15") (pinfunction "DDP_15") (pintype "bidirectional"))
    )
    (net (code "78") (name "unconnected-(IC1-OUT0-Pad7)") (class "Default")
      (node (ref "IC1") (pin "7") (pinfunction "OUT0_7") (pintype "bidirectional"))
    )
    (net (code "79") (name "unconnected-(IC1-OUT2-Pad9)") (class "Default")
      (node (ref "IC1") (pin "9") (pinfunction "OUT2_9") (pintype "bidirectional"))
    )
    (net (code "80") (name "unconnected-(IC1-OUT8-Pad15)") (class "Default")
      (node (ref "IC1") (pin "15") (pinfunction "OUT8_15") (pintype "bidirectional"))
    )
    (net (code "81") (name "unconnected-(IC2A-O-Pad12)") (class "Default")
      (node (ref "IC2") (pin "12") (pinfunction "O_12") (pintype "output"))
    )
    (net (code "82") (name "unconnected-(IC2B-O-Pad10)") (class "Default")
      (node (ref "IC2") (pin "10") (pinfunction "O_10") (pintype "output"))
    )
    (net (code "83") (name "unconnected-(IC2C-O-Pad8)") (class "Default")
      (node (ref "IC2") (pin "8") (pinfunction "O_8") (pintype "output"))
    )
    (net (code "84") (name "unconnected-(IC2D-O-Pad2)") (class "Default")
      (node (ref "IC2") (pin "2") (pinfunction "O_2") (pintype "output"))
    )
    (net (code "85") (name "unconnected-(IC2E-I-Pad3)") (class "Default")
      (node (ref "IC2") (pin "3") (pinfunction "I_3") (pintype "input"))
    )
    (net (code "86") (name "unconnected-(IC2E-O-Pad4)") (class "Default")
      (node (ref "IC2") (pin "4") (pinfunction "O_4") (pintype "output"))
    )
    (net (code "87") (name "unconnected-(U$1-SCL-Pad9)") (class "Default")
      (node (ref "U$1") (pin "9") (pinfunction "SCL_9") (pintype "bidirectional"))
    )
    (net (code "88") (name "unconnected-(U$1-SDA-Pad10)") (class "Default")
      (node (ref "U$1") (pin "10") (pinfunction "SDA_10") (pintype "bidirectional"))
    )
    (net (code "89") (name "unconnected-(U$1-SIN-Pad24)") (class "Default")
      (node (ref "U$1") (pin "24") (pinfunction "SIN_24") (pintype "bidirectional"))
    )
    (net (code "90") (name "unconnected-(X1-PadID)") (class "Default")
      (node (ref "X1") (pin "ID") (pinfunction "ID_ID") (pintype "bidirectional"))
    )
  )
)
